# TwoMegCoCo_MMU_v1_1.net
KiCad netlist of a schematic drawn in EAGLE
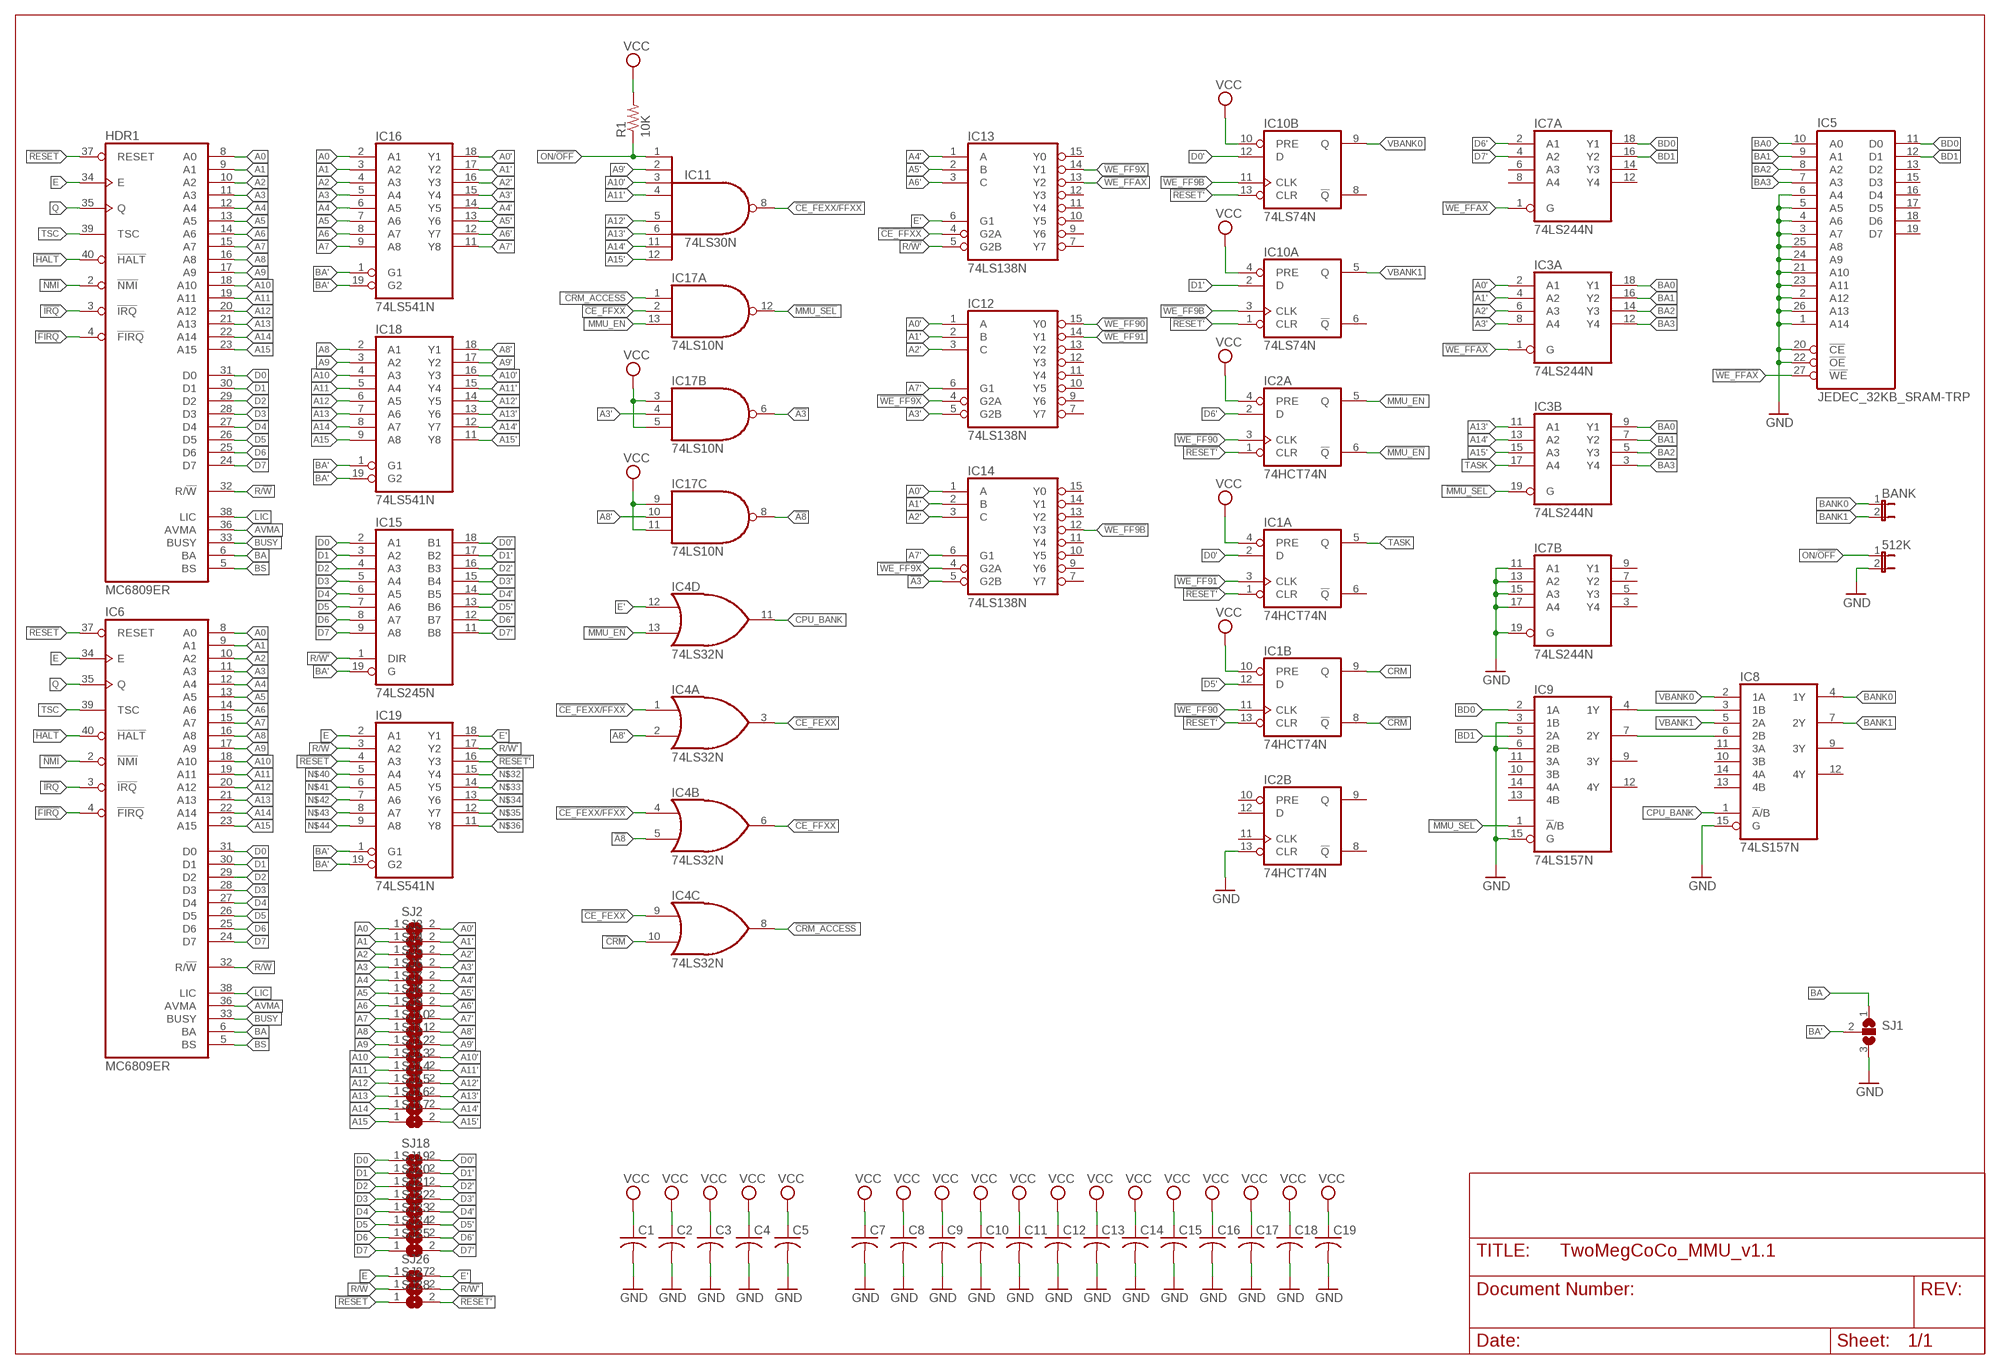
[diagram p0: schematic, sheet 1]

(export (version "E")
  (design (tool "Eeschema 10.0.6"))
  (components
    (comp (ref "512K")
      (value "JP1E")
      (footprint "eagle-import:JP1")
      (libsource (lib "eagle-import") (part "JP1E"))
    )
    (comp (ref "BANK")
      (value "JP1E")
      (footprint "eagle-import:JP1")
      (libsource (lib "eagle-import") (part "JP1E"))
    )
    (comp (ref "C1")
      (value "C-US025-025X050")
      (footprint "eagle-import:C025-025X050")
      (libsource (lib "eagle-import") (part "C-US025-025X050"))
    )
    (comp (ref "C2")
      (value "C-US025-025X050")
      (footprint "eagle-import:C025-025X050")
      (libsource (lib "eagle-import") (part "C-US025-025X050"))
    )
    (comp (ref "C3")
      (value "C-US025-025X050")
      (footprint "eagle-import:C025-025X050")
      (libsource (lib "eagle-import") (part "C-US025-025X050"))
    )
    (comp (ref "C4")
      (value "C-US025-025X050")
      (footprint "eagle-import:C025-025X050")
      (libsource (lib "eagle-import") (part "C-US025-025X050"))
    )
    (comp (ref "C5")
      (value "C-US025-025X050")
      (footprint "eagle-import:C025-025X050")
      (libsource (lib "eagle-import") (part "C-US025-025X050"))
    )
    (comp (ref "C7")
      (value "C-US025-025X050")
      (footprint "eagle-import:C025-025X050")
      (libsource (lib "eagle-import") (part "C-US025-025X050"))
    )
    (comp (ref "C8")
      (value "C-US025-025X050")
      (footprint "eagle-import:C025-025X050")
      (libsource (lib "eagle-import") (part "C-US025-025X050"))
    )
    (comp (ref "C9")
      (value "C-US025-025X050")
      (footprint "eagle-import:C025-025X050")
      (libsource (lib "eagle-import") (part "C-US025-025X050"))
    )
    (comp (ref "C10")
      (value "C-US025-025X050")
      (footprint "eagle-import:C025-025X050")
      (libsource (lib "eagle-import") (part "C-US025-025X050"))
    )
    (comp (ref "C11")
      (value "C-US025-025X050")
      (footprint "eagle-import:C025-025X050")
      (libsource (lib "eagle-import") (part "C-US025-025X050"))
    )
    (comp (ref "C12")
      (value "C-US025-025X050")
      (footprint "eagle-import:C025-025X050")
      (libsource (lib "eagle-import") (part "C-US025-025X050"))
    )
    (comp (ref "C13")
      (value "C-US025-025X050")
      (footprint "eagle-import:C025-025X050")
      (libsource (lib "eagle-import") (part "C-US025-025X050"))
    )
    (comp (ref "C14")
      (value "C-US025-025X050")
      (footprint "eagle-import:C025-025X050")
      (libsource (lib "eagle-import") (part "C-US025-025X050"))
    )
    (comp (ref "C15")
      (value "C-US025-025X050")
      (footprint "eagle-import:C025-025X050")
      (libsource (lib "eagle-import") (part "C-US025-025X050"))
    )
    (comp (ref "C16")
      (value "C-US025-025X050")
      (footprint "eagle-import:C025-025X050")
      (libsource (lib "eagle-import") (part "C-US025-025X050"))
    )
    (comp (ref "C17")
      (value "C-US025-025X050")
      (footprint "eagle-import:C025-025X050")
      (libsource (lib "eagle-import") (part "C-US025-025X050"))
    )
    (comp (ref "C18")
      (value "C-US025-025X050")
      (footprint "eagle-import:C025-025X050")
      (libsource (lib "eagle-import") (part "C-US025-025X050"))
    )
    (comp (ref "C19")
      (value "C-US025-025X050")
      (footprint "eagle-import:C025-025X050")
      (libsource (lib "eagle-import") (part "C-US025-025X050"))
    )
    (comp (ref "HDR1")
      (value "MC6809ER")
      (footprint "eagle-import:DIL40-ROUNDPAD")
      (libsource (lib "eagle-import") (part "MC6809ER"))
    )
    (comp (ref "IC1")
      (value "74HCT74N")
      (footprint "eagle-import:DIL14-RP")
      (libsource (lib "eagle-import") (part "7474NHCT"))
    )
    (comp (ref "IC2")
      (value "74HCT74N")
      (footprint "eagle-import:DIL14-RP")
      (libsource (lib "eagle-import") (part "7474NHCT"))
    )
    (comp (ref "IC3")
      (value "74LS244N")
      (footprint "eagle-import:DIL20-RP")
      (libsource (lib "eagle-import") (part "74244NLS"))
    )
    (comp (ref "IC4")
      (value "74LS32N")
      (footprint "eagle-import:DIL14-RP")
      (libsource (lib "eagle-import") (part "7432NLS"))
    )
    (comp (ref "IC5")
      (value "JEDEC_32KB_SRAM-TRP")
      (footprint "eagle-import:DIL28-3-RP")
      (libsource (lib "eagle-import") (part "JEDEC_32KB_SRAM-TRP"))
    )
    (comp (ref "IC6")
      (value "MC6809ER")
      (footprint "eagle-import:DIL40-ROUNDPAD")
      (libsource (lib "eagle-import") (part "MC6809ER"))
    )
    (comp (ref "IC7")
      (value "74LS244N")
      (footprint "eagle-import:DIL20-RP")
      (libsource (lib "eagle-import") (part "74244NLS"))
    )
    (comp (ref "IC8")
      (value "74LS157N")
      (footprint "eagle-import:DIL16-RP")
      (libsource (lib "eagle-import") (part "74157NLS"))
    )
    (comp (ref "IC9")
      (value "74LS157N")
      (footprint "eagle-import:DIL16-RP")
      (libsource (lib "eagle-import") (part "74157NLS"))
    )
    (comp (ref "IC10")
      (value "74LS74N")
      (footprint "eagle-import:DIL14-RP")
      (libsource (lib "eagle-import") (part "7474NLS"))
    )
    (comp (ref "IC11")
      (value "74LS30N")
      (footprint "eagle-import:DIL14-RP")
      (libsource (lib "eagle-import") (part "7430NLS"))
    )
    (comp (ref "IC12")
      (value "74LS138N")
      (footprint "eagle-import:DIL16-RP")
      (libsource (lib "eagle-import") (part "74138NLS"))
    )
    (comp (ref "IC13")
      (value "74LS138N")
      (footprint "eagle-import:DIL16-RP")
      (libsource (lib "eagle-import") (part "74138NLS"))
    )
    (comp (ref "IC14")
      (value "74LS138N")
      (footprint "eagle-import:DIL16-RP")
      (libsource (lib "eagle-import") (part "74138NLS"))
    )
    (comp (ref "IC15")
      (value "74LS245N")
      (footprint "eagle-import:DIL20-RP")
      (libsource (lib "eagle-import") (part "74245NLS"))
    )
    (comp (ref "IC16")
      (value "74LS541N")
      (footprint "eagle-import:DIL20-RP")
      (libsource (lib "eagle-import") (part "74541NLS"))
    )
    (comp (ref "IC17")
      (value "74LS10N")
      (footprint "eagle-import:DIL14-RP")
      (libsource (lib "eagle-import") (part "7410NLS"))
    )
    (comp (ref "IC18")
      (value "74LS541N")
      (footprint "eagle-import:DIL20-RP")
      (libsource (lib "eagle-import") (part "74541NLS"))
    )
    (comp (ref "IC19")
      (value "74LS541N")
      (footprint "eagle-import:DIL20-RP")
      (libsource (lib "eagle-import") (part "74541NLS"))
    )
    (comp (ref "R1")
      (value "10K")
      (footprint "eagle-import:0204_7")
      (libsource (lib "eagle-import") (part "R-US_0204/7"))
    )
    (comp (ref "SJ1")
      (value "SJ2W")
      (footprint "eagle-import:SJ_2")
      (libsource (lib "eagle-import") (part "SJ2W"))
    )
    (comp (ref "SJ2") (value "SJ") (footprint "eagle-import:SJ") (libsource (lib "eagle-import") (part "SJ")))
    (comp (ref "SJ3") (value "SJ") (footprint "eagle-import:SJ") (libsource (lib "eagle-import") (part "SJ")))
    (comp (ref "SJ4") (value "SJ") (footprint "eagle-import:SJ") (libsource (lib "eagle-import") (part "SJ")))
    (comp (ref "SJ5") (value "SJ") (footprint "eagle-import:SJ") (libsource (lib "eagle-import") (part "SJ")))
    (comp (ref "SJ6") (value "SJ") (footprint "eagle-import:SJ") (libsource (lib "eagle-import") (part "SJ")))
    (comp (ref "SJ7") (value "SJ") (footprint "eagle-import:SJ") (libsource (lib "eagle-import") (part "SJ")))
    (comp (ref "SJ8") (value "SJ") (footprint "eagle-import:SJ") (libsource (lib "eagle-import") (part "SJ")))
    (comp (ref "SJ9") (value "SJ") (footprint "eagle-import:SJ") (libsource (lib "eagle-import") (part "SJ")))
    (comp (ref "SJ10")
      (value "SJ")
      (footprint "eagle-import:SJ")
      (libsource (lib "eagle-import") (part "SJ"))
    )
    (comp (ref "SJ11")
      (value "SJ")
      (footprint "eagle-import:SJ")
      (libsource (lib "eagle-import") (part "SJ"))
    )
    (comp (ref "SJ12")
      (value "SJ")
      (footprint "eagle-import:SJ")
      (libsource (lib "eagle-import") (part "SJ"))
    )
    (comp (ref "SJ13")
      (value "SJ")
      (footprint "eagle-import:SJ")
      (libsource (lib "eagle-import") (part "SJ"))
    )
    (comp (ref "SJ14")
      (value "SJ")
      (footprint "eagle-import:SJ")
      (libsource (lib "eagle-import") (part "SJ"))
    )
    (comp (ref "SJ15")
      (value "SJ")
      (footprint "eagle-import:SJ")
      (libsource (lib "eagle-import") (part "SJ"))
    )
    (comp (ref "SJ16")
      (value "SJ")
      (footprint "eagle-import:SJ")
      (libsource (lib "eagle-import") (part "SJ"))
    )
    (comp (ref "SJ17")
      (value "SJ")
      (footprint "eagle-import:SJ")
      (libsource (lib "eagle-import") (part "SJ"))
    )
    (comp (ref "SJ18")
      (value "SJ")
      (footprint "eagle-import:SJ")
      (libsource (lib "eagle-import") (part "SJ"))
    )
    (comp (ref "SJ19")
      (value "SJ")
      (footprint "eagle-import:SJ")
      (libsource (lib "eagle-import") (part "SJ"))
    )
    (comp (ref "SJ20")
      (value "SJ")
      (footprint "eagle-import:SJ")
      (libsource (lib "eagle-import") (part "SJ"))
    )
    (comp (ref "SJ21")
      (value "SJ")
      (footprint "eagle-import:SJ")
      (libsource (lib "eagle-import") (part "SJ"))
    )
    (comp (ref "SJ22")
      (value "SJ")
      (footprint "eagle-import:SJ")
      (libsource (lib "eagle-import") (part "SJ"))
    )
    (comp (ref "SJ23")
      (value "SJ")
      (footprint "eagle-import:SJ")
      (libsource (lib "eagle-import") (part "SJ"))
    )
    (comp (ref "SJ24")
      (value "SJ")
      (footprint "eagle-import:SJ")
      (libsource (lib "eagle-import") (part "SJ"))
    )
    (comp (ref "SJ25")
      (value "SJ")
      (footprint "eagle-import:SJ")
      (libsource (lib "eagle-import") (part "SJ"))
    )
    (comp (ref "SJ26")
      (value "SJ")
      (footprint "eagle-import:SJ")
      (libsource (lib "eagle-import") (part "SJ"))
    )
    (comp (ref "SJ27")
      (value "SJ")
      (footprint "eagle-import:SJ")
      (libsource (lib "eagle-import") (part "SJ"))
    )
    (comp (ref "SJ28")
      (value "SJ")
      (footprint "eagle-import:SJ")
      (libsource (lib "eagle-import") (part "SJ"))
    )
  )
  (nets
    (net (code "1") (name "/ON{slash}~{OFF}") (class "Default")
      (node (ref "512K") (pin "1") (pinfunction "1_1") (pintype "passive"))
      (node (ref "IC11") (pin "1") (pinfunction "I0_1") (pintype "input"))
      (node (ref "R1") (pin "1") (pinfunction "1_1") (pintype "passive"))
    )
    (net (code "2") (name "/R{slash}~{W'}") (class "Default")
      (node (ref "IC13") (pin "5") (pinfunction "G2B_5") (pintype "input"))
      (node (ref "IC15") (pin "1") (pinfunction "DIR_1") (pintype "input"))
      (node (ref "IC19") (pin "17") (pinfunction "Y2_17") (pintype "tri_state"))
      (node (ref "SJ27") (pin "2") (pinfunction "2_2") (pintype "passive"))
    )
    (net (code "3") (name "/R{slash}~{W}") (class "Default")
      (node (ref "HDR1") (pin "32") (pinfunction "R/~{W}_32") (pintype "output"))
      (node (ref "IC19") (pin "3") (pinfunction "A2_3") (pintype "input"))
      (node (ref "IC6") (pin "32") (pinfunction "R/~{W}_32") (pintype "output"))
      (node (ref "SJ27") (pin "1") (pinfunction "1_1") (pintype "passive"))
    )
    (net (code "4") (name "/~{A3}") (class "Default")
      (node (ref "IC14") (pin "5") (pinfunction "G2B_5") (pintype "input"))
      (node (ref "IC17") (pin "6") (pinfunction "O_6") (pintype "output"))
    )
    (net (code "5") (name "/~{A8}") (class "Default")
      (node (ref "IC17") (pin "8") (pinfunction "O_8") (pintype "output"))
      (node (ref "IC4") (pin "5") (pinfunction "I1_5") (pintype "input"))
    )
    (net (code "6") (name "/~{CE_FEXX{slash}FFXX}") (class "Default")
      (node (ref "IC11") (pin "8") (pinfunction "O_8") (pintype "output"))
      (node (ref "IC4") (pin "1") (pinfunction "I0_1") (pintype "input"))
      (node (ref "IC4") (pin "4") (pinfunction "I0_4") (pintype "input"))
    )
    (net (code "7") (name "/~{CE_FEXX}") (class "Default")
      (node (ref "IC4") (pin "3") (pinfunction "O_3") (pintype "output"))
      (node (ref "IC4") (pin "9") (pinfunction "I0_9") (pintype "input"))
    )
    (net (code "8") (name "/~{CE_FFXX}") (class "Default")
      (node (ref "IC13") (pin "4") (pinfunction "G2A_4") (pintype "input"))
      (node (ref "IC17") (pin "2") (pinfunction "I1_2") (pintype "input"))
      (node (ref "IC4") (pin "6") (pinfunction "O_6") (pintype "output"))
    )
    (net (code "9") (name "/~{CRM_ACCESS}") (class "Default")
      (node (ref "IC17") (pin "1") (pinfunction "I0_1") (pintype "input"))
      (node (ref "IC4") (pin "8") (pinfunction "O_8") (pintype "output"))
    )
    (net (code "10") (name "/~{CRM}") (class "Default")
      (node (ref "IC1") (pin "8") (pinfunction "~{Q}_8") (pintype "output"))
      (node (ref "IC4") (pin "10") (pinfunction "I1_10") (pintype "input"))
    )
    (net (code "11") (name "/~{FIRQ}") (class "Default")
      (node (ref "HDR1") (pin "4") (pinfunction "~{FIRQ}_4") (pintype "open_collector"))
      (node (ref "IC6") (pin "4") (pinfunction "~{FIRQ}_4") (pintype "open_collector"))
    )
    (net (code "12") (name "/~{HALT}") (class "Default")
      (node (ref "HDR1") (pin "40") (pinfunction "~{HALT}_40") (pintype "open_collector"))
      (node (ref "IC6") (pin "40") (pinfunction "~{HALT}_40") (pintype "open_collector"))
    )
    (net (code "13") (name "/~{IRQ}") (class "Default")
      (node (ref "HDR1") (pin "3") (pinfunction "~{IRQ}_3") (pintype "open_collector"))
      (node (ref "IC6") (pin "3") (pinfunction "~{IRQ}_3") (pintype "open_collector"))
    )
    (net (code "14") (name "/~{MMU_EN}") (class "Default")
      (node (ref "IC2") (pin "6") (pinfunction "~{Q}_6") (pintype "output"))
      (node (ref "IC4") (pin "13") (pinfunction "I1_13") (pintype "input"))
    )
    (net (code "15") (name "/~{MMU_SEL}") (class "Default")
      (node (ref "IC17") (pin "12") (pinfunction "O_12") (pintype "output"))
      (node (ref "IC3") (pin "19") (pinfunction "G_19") (pintype "input"))
      (node (ref "IC9") (pin "1") (pinfunction "~{A}/B_1") (pintype "input"))
    )
    (net (code "16") (name "/~{NMI}") (class "Default")
      (node (ref "HDR1") (pin "2") (pinfunction "~{NMI}_2") (pintype "open_collector"))
      (node (ref "IC6") (pin "2") (pinfunction "~{NMI}_2") (pintype "open_collector"))
    )
    (net (code "17") (name "/~{RESET'}") (class "Default")
      (node (ref "IC1") (pin "1") (pinfunction "CLR_1") (pintype "input"))
      (node (ref "IC1") (pin "13") (pinfunction "CLR_13") (pintype "input"))
      (node (ref "IC10") (pin "1") (pinfunction "CLR_1") (pintype "input"))
      (node (ref "IC10") (pin "13") (pinfunction "CLR_13") (pintype "input"))
      (node (ref "IC19") (pin "16") (pinfunction "Y3_16") (pintype "tri_state"))
      (node (ref "IC2") (pin "1") (pinfunction "CLR_1") (pintype "input"))
      (node (ref "SJ28") (pin "2") (pinfunction "2_2") (pintype "passive"))
    )
    (net (code "18") (name "/~{RESET}") (class "Default")
      (node (ref "HDR1") (pin "37") (pinfunction "RESET_37") (pintype "input"))
      (node (ref "IC19") (pin "4") (pinfunction "A3_4") (pintype "input"))
      (node (ref "IC6") (pin "37") (pinfunction "RESET_37") (pintype "input"))
      (node (ref "SJ28") (pin "1") (pinfunction "1_1") (pintype "passive"))
    )
    (net (code "19") (name "/~{WE_FF9B}") (class "Default")
      (node (ref "IC10") (pin "11") (pinfunction "CLK_11") (pintype "input"))
      (node (ref "IC10") (pin "3") (pinfunction "CLK_3") (pintype "input"))
      (node (ref "IC14") (pin "12") (pinfunction "Y3_12") (pintype "output"))
    )
    (net (code "20") (name "/~{WE_FF9X}") (class "Default")
      (node (ref "IC12") (pin "4") (pinfunction "G2A_4") (pintype "input"))
      (node (ref "IC13") (pin "14") (pinfunction "Y1_14") (pintype "output"))
      (node (ref "IC14") (pin "4") (pinfunction "G2A_4") (pintype "input"))
    )
    (net (code "21") (name "/~{WE_FF90}") (class "Default")
      (node (ref "IC1") (pin "11") (pinfunction "CLK_11") (pintype "input"))
      (node (ref "IC12") (pin "15") (pinfunction "Y0_15") (pintype "output"))
      (node (ref "IC2") (pin "3") (pinfunction "CLK_3") (pintype "input"))
    )
    (net (code "22") (name "/~{WE_FF91}") (class "Default")
      (node (ref "IC1") (pin "3") (pinfunction "CLK_3") (pintype "input"))
      (node (ref "IC12") (pin "14") (pinfunction "Y1_14") (pintype "output"))
    )
    (net (code "23") (name "/~{WE_FFAX}") (class "Default")
      (node (ref "IC13") (pin "13") (pinfunction "Y2_13") (pintype "output"))
      (node (ref "IC3") (pin "1") (pinfunction "G_1") (pintype "input"))
      (node (ref "IC5") (pin "27") (pinfunction "~{WE}_27") (pintype "input"))
      (node (ref "IC7") (pin "1") (pinfunction "G_1") (pintype "input"))
    )
    (net (code "24") (name "A0") (class "Default")
      (node (ref "HDR1") (pin "8") (pinfunction "A0_8") (pintype "tri_state"))
      (node (ref "IC16") (pin "2") (pinfunction "A1_2") (pintype "input"))
      (node (ref "IC6") (pin "8") (pinfunction "A0_8") (pintype "tri_state"))
      (node (ref "SJ2") (pin "1") (pinfunction "1_1") (pintype "passive"))
    )
    (net (code "25") (name "A0'") (class "Default")
      (node (ref "IC12") (pin "1") (pinfunction "A_1") (pintype "input"))
      (node (ref "IC14") (pin "1") (pinfunction "A_1") (pintype "input"))
      (node (ref "IC16") (pin "18") (pinfunction "Y1_18") (pintype "tri_state"))
      (node (ref "IC3") (pin "2") (pinfunction "A1_2") (pintype "input"))
      (node (ref "SJ2") (pin "2") (pinfunction "2_2") (pintype "passive"))
    )
    (net (code "26") (name "A1") (class "Default")
      (node (ref "HDR1") (pin "9") (pinfunction "A1_9") (pintype "tri_state"))
      (node (ref "IC16") (pin "3") (pinfunction "A2_3") (pintype "input"))
      (node (ref "IC6") (pin "9") (pinfunction "A1_9") (pintype "tri_state"))
      (node (ref "SJ3") (pin "1") (pinfunction "1_1") (pintype "passive"))
    )
    (net (code "27") (name "A1'") (class "Default")
      (node (ref "IC12") (pin "2") (pinfunction "B_2") (pintype "input"))
      (node (ref "IC14") (pin "2") (pinfunction "B_2") (pintype "input"))
      (node (ref "IC16") (pin "17") (pinfunction "Y2_17") (pintype "tri_state"))
      (node (ref "IC3") (pin "4") (pinfunction "A2_4") (pintype "input"))
      (node (ref "SJ3") (pin "2") (pinfunction "2_2") (pintype "passive"))
    )
    (net (code "28") (name "A2") (class "Default")
      (node (ref "HDR1") (pin "10") (pinfunction "A2_10") (pintype "tri_state"))
      (node (ref "IC16") (pin "4") (pinfunction "A3_4") (pintype "input"))
      (node (ref "IC6") (pin "10") (pinfunction "A2_10") (pintype "tri_state"))
      (node (ref "SJ4") (pin "1") (pinfunction "1_1") (pintype "passive"))
    )
    (net (code "29") (name "A2'") (class "Default")
      (node (ref "IC12") (pin "3") (pinfunction "C_3") (pintype "input"))
      (node (ref "IC14") (pin "3") (pinfunction "C_3") (pintype "input"))
      (node (ref "IC16") (pin "16") (pinfunction "Y3_16") (pintype "tri_state"))
      (node (ref "IC3") (pin "6") (pinfunction "A3_6") (pintype "input"))
      (node (ref "SJ4") (pin "2") (pinfunction "2_2") (pintype "passive"))
    )
    (net (code "30") (name "A3") (class "Default")
      (node (ref "HDR1") (pin "11") (pinfunction "A3_11") (pintype "tri_state"))
      (node (ref "IC16") (pin "5") (pinfunction "A4_5") (pintype "input"))
      (node (ref "IC6") (pin "11") (pinfunction "A3_11") (pintype "tri_state"))
      (node (ref "SJ5") (pin "1") (pinfunction "1_1") (pintype "passive"))
    )
    (net (code "31") (name "A3'") (class "Default")
      (node (ref "IC12") (pin "5") (pinfunction "G2B_5") (pintype "input"))
      (node (ref "IC16") (pin "15") (pinfunction "Y4_15") (pintype "tri_state"))
      (node (ref "IC17") (pin "4") (pinfunction "I1_4") (pintype "input"))
      (node (ref "IC3") (pin "8") (pinfunction "A4_8") (pintype "input"))
      (node (ref "SJ5") (pin "2") (pinfunction "2_2") (pintype "passive"))
    )
    (net (code "32") (name "A4") (class "Default")
      (node (ref "HDR1") (pin "12") (pinfunction "A4_12") (pintype "tri_state"))
      (node (ref "IC16") (pin "6") (pinfunction "A5_6") (pintype "input"))
      (node (ref "IC6") (pin "12") (pinfunction "A4_12") (pintype "tri_state"))
      (node (ref "SJ6") (pin "1") (pinfunction "1_1") (pintype "passive"))
    )
    (net (code "33") (name "A4'") (class "Default")
      (node (ref "IC13") (pin "1") (pinfunction "A_1") (pintype "input"))
      (node (ref "IC16") (pin "14") (pinfunction "Y5_14") (pintype "tri_state"))
      (node (ref "SJ6") (pin "2") (pinfunction "2_2") (pintype "passive"))
    )
    (net (code "34") (name "A5") (class "Default")
      (node (ref "HDR1") (pin "13") (pinfunction "A5_13") (pintype "tri_state"))
      (node (ref "IC16") (pin "7") (pinfunction "A6_7") (pintype "input"))
      (node (ref "IC6") (pin "13") (pinfunction "A5_13") (pintype "tri_state"))
      (node (ref "SJ7") (pin "1") (pinfunction "1_1") (pintype "passive"))
    )
    (net (code "35") (name "A5'") (class "Default")
      (node (ref "IC13") (pin "2") (pinfunction "B_2") (pintype "input"))
      (node (ref "IC16") (pin "13") (pinfunction "Y6_13") (pintype "tri_state"))
      (node (ref "SJ7") (pin "2") (pinfunction "2_2") (pintype "passive"))
    )
    (net (code "36") (name "A6") (class "Default")
      (node (ref "HDR1") (pin "14") (pinfunction "A6_14") (pintype "tri_state"))
      (node (ref "IC16") (pin "8") (pinfunction "A7_8") (pintype "input"))
      (node (ref "IC6") (pin "14") (pinfunction "A6_14") (pintype "tri_state"))
      (node (ref "SJ8") (pin "1") (pinfunction "1_1") (pintype "passive"))
    )
    (net (code "37") (name "A6'") (class "Default")
      (node (ref "IC13") (pin "3") (pinfunction "C_3") (pintype "input"))
      (node (ref "IC16") (pin "12") (pinfunction "Y7_12") (pintype "tri_state"))
      (node (ref "SJ8") (pin "2") (pinfunction "2_2") (pintype "passive"))
    )
    (net (code "38") (name "A7") (class "Default")
      (node (ref "HDR1") (pin "15") (pinfunction "A7_15") (pintype "tri_state"))
      (node (ref "IC16") (pin "9") (pinfunction "A8_9") (pintype "input"))
      (node (ref "IC6") (pin "15") (pinfunction "A7_15") (pintype "tri_state"))
      (node (ref "SJ9") (pin "1") (pinfunction "1_1") (pintype "passive"))
    )
    (net (code "39") (name "A7'") (class "Default")
      (node (ref "IC12") (pin "6") (pinfunction "G1_6") (pintype "input"))
      (node (ref "IC14") (pin "6") (pinfunction "G1_6") (pintype "input"))
      (node (ref "IC16") (pin "11") (pinfunction "Y8_11") (pintype "tri_state"))
      (node (ref "SJ9") (pin "2") (pinfunction "2_2") (pintype "passive"))
    )
    (net (code "40") (name "A8") (class "Default")
      (node (ref "HDR1") (pin "16") (pinfunction "A8_16") (pintype "tri_state"))
      (node (ref "IC18") (pin "2") (pinfunction "A1_2") (pintype "input"))
      (node (ref "IC6") (pin "16") (pinfunction "A8_16") (pintype "tri_state"))
      (node (ref "SJ10") (pin "1") (pinfunction "1_1") (pintype "passive"))
    )
    (net (code "41") (name "A8'") (class "Default")
      (node (ref "IC17") (pin "10") (pinfunction "I1_10") (pintype "input"))
      (node (ref "IC18") (pin "18") (pinfunction "Y1_18") (pintype "tri_state"))
      (node (ref "IC4") (pin "2") (pinfunction "I1_2") (pintype "input"))
      (node (ref "SJ10") (pin "2") (pinfunction "2_2") (pintype "passive"))
    )
    (net (code "42") (name "A9") (class "Default")
      (node (ref "HDR1") (pin "17") (pinfunction "A9_17") (pintype "tri_state"))
      (node (ref "IC18") (pin "3") (pinfunction "A2_3") (pintype "input"))
      (node (ref "IC6") (pin "17") (pinfunction "A9_17") (pintype "tri_state"))
      (node (ref "SJ11") (pin "1") (pinfunction "1_1") (pintype "passive"))
    )
    (net (code "43") (name "A9'") (class "Default")
      (node (ref "IC11") (pin "2") (pinfunction "I1_2") (pintype "input"))
      (node (ref "IC18") (pin "17") (pinfunction "Y2_17") (pintype "tri_state"))
      (node (ref "SJ11") (pin "2") (pinfunction "2_2") (pintype "passive"))
    )
    (net (code "44") (name "A10") (class "Default")
      (node (ref "HDR1") (pin "18") (pinfunction "A10_18") (pintype "tri_state"))
      (node (ref "IC18") (pin "4") (pinfunction "A3_4") (pintype "input"))
      (node (ref "IC6") (pin "18") (pinfunction "A10_18") (pintype "tri_state"))
      (node (ref "SJ12") (pin "1") (pinfunction "1_1") (pintype "passive"))
    )
    (net (code "45") (name "A10'") (class "Default")
      (node (ref "IC11") (pin "3") (pinfunction "I2_3") (pintype "input"))
      (node (ref "IC18") (pin "16") (pinfunction "Y3_16") (pintype "tri_state"))
      (node (ref "SJ12") (pin "2") (pinfunction "2_2") (pintype "passive"))
    )
    (net (code "46") (name "A11") (class "Default")
      (node (ref "HDR1") (pin "19") (pinfunction "A11_19") (pintype "tri_state"))
      (node (ref "IC18") (pin "5") (pinfunction "A4_5") (pintype "input"))
      (node (ref "IC6") (pin "19") (pinfunction "A11_19") (pintype "tri_state"))
      (node (ref "SJ13") (pin "1") (pinfunction "1_1") (pintype "passive"))
    )
    (net (code "47") (name "A11'") (class "Default")
      (node (ref "IC11") (pin "4") (pinfunction "I3_4") (pintype "input"))
      (node (ref "IC18") (pin "15") (pinfunction "Y4_15") (pintype "tri_state"))
      (node (ref "SJ13") (pin "2") (pinfunction "2_2") (pintype "passive"))
    )
    (net (code "48") (name "A12") (class "Default")
      (node (ref "HDR1") (pin "20") (pinfunction "A12_20") (pintype "tri_state"))
      (node (ref "IC18") (pin "6") (pinfunction "A5_6") (pintype "input"))
      (node (ref "IC6") (pin "20") (pinfunction "A12_20") (pintype "tri_state"))
      (node (ref "SJ14") (pin "1") (pinfunction "1_1") (pintype "passive"))
    )
    (net (code "49") (name "A12'") (class "Default")
      (node (ref "IC11") (pin "5") (pinfunction "I4_5") (pintype "input"))
      (node (ref "IC18") (pin "14") (pinfunction "Y5_14") (pintype "tri_state"))
      (node (ref "SJ14") (pin "2") (pinfunction "2_2") (pintype "passive"))
    )
    (net (code "50") (name "A13") (class "Default")
      (node (ref "HDR1") (pin "21") (pinfunction "A13_21") (pintype "tri_state"))
      (node (ref "IC18") (pin "7") (pinfunction "A6_7") (pintype "input"))
      (node (ref "IC6") (pin "21") (pinfunction "A13_21") (pintype "tri_state"))
      (node (ref "SJ15") (pin "1") (pinfunction "1_1") (pintype "passive"))
    )
    (net (code "51") (name "A13'") (class "Default")
      (node (ref "IC11") (pin "6") (pinfunction "I5_6") (pintype "input"))
      (node (ref "IC18") (pin "13") (pinfunction "Y6_13") (pintype "tri_state"))
      (node (ref "IC3") (pin "11") (pinfunction "A1_11") (pintype "input"))
      (node (ref "SJ15") (pin "2") (pinfunction "2_2") (pintype "passive"))
    )
    (net (code "52") (name "A14") (class "Default")
      (node (ref "HDR1") (pin "22") (pinfunction "A14_22") (pintype "tri_state"))
      (node (ref "IC18") (pin "8") (pinfunction "A7_8") (pintype "input"))
      (node (ref "IC6") (pin "22") (pinfunction "A14_22") (pintype "tri_state"))
      (node (ref "SJ16") (pin "1") (pinfunction "1_1") (pintype "passive"))
    )
    (net (code "53") (name "A14'") (class "Default")
      (node (ref "IC11") (pin "11") (pinfunction "I6_11") (pintype "input"))
      (node (ref "IC18") (pin "12") (pinfunction "Y7_12") (pintype "tri_state"))
      (node (ref "IC3") (pin "13") (pinfunction "A2_13") (pintype "input"))
      (node (ref "SJ16") (pin "2") (pinfunction "2_2") (pintype "passive"))
    )
    (net (code "54") (name "A15") (class "Default")
      (node (ref "HDR1") (pin "23") (pinfunction "A15_23") (pintype "tri_state"))
      (node (ref "IC18") (pin "9") (pinfunction "A8_9") (pintype "input"))
      (node (ref "IC6") (pin "23") (pinfunction "A15_23") (pintype "tri_state"))
      (node (ref "SJ17") (pin "1") (pinfunction "1_1") (pintype "passive"))
    )
    (net (code "55") (name "A15'") (class "Default")
      (node (ref "IC11") (pin "12") (pinfunction "I7_12") (pintype "input"))
      (node (ref "IC18") (pin "11") (pinfunction "Y8_11") (pintype "tri_state"))
      (node (ref "IC3") (pin "15") (pinfunction "A3_15") (pintype "input"))
      (node (ref "SJ17") (pin "2") (pinfunction "2_2") (pintype "passive"))
    )
    (net (code "56") (name "AVMA") (class "Default")
      (node (ref "HDR1") (pin "36") (pinfunction "AVMA_36") (pintype "output"))
      (node (ref "IC6") (pin "36") (pinfunction "AVMA_36") (pintype "output"))
    )
    (net (code "57") (name "BA") (class "Default")
      (node (ref "HDR1") (pin "6") (pinfunction "BA_6") (pintype "output"))
      (node (ref "IC6") (pin "6") (pinfunction "BA_6") (pintype "output"))
      (node (ref "SJ1") (pin "1") (pinfunction "1_1") (pintype "passive"))
    )
    (net (code "58") (name "BA'") (class "Default")
      (node (ref "IC15") (pin "19") (pinfunction "G_19") (pintype "input"))
      (node (ref "IC16") (pin "1") (pinfunction "G1_1") (pintype "input"))
      (node (ref "IC16") (pin "19") (pinfunction "G2_19") (pintype "input"))
      (node (ref "IC18") (pin "1") (pinfunction "G1_1") (pintype "input"))
      (node (ref "IC18") (pin "19") (pinfunction "G2_19") (pintype "input"))
      (node (ref "IC19") (pin "1") (pinfunction "G1_1") (pintype "input"))
      (node (ref "IC19") (pin "19") (pinfunction "G2_19") (pintype "input"))
      (node (ref "SJ1") (pin "2") (pinfunction "2_2") (pintype "passive"))
    )
    (net (code "59") (name "BA0") (class "Default")
      (node (ref "IC3") (pin "18") (pinfunction "Y1_18") (pintype "tri_state"))
      (node (ref "IC3") (pin "9") (pinfunction "Y1_9") (pintype "tri_state"))
      (node (ref "IC5") (pin "10") (pinfunction "A0_10") (pintype "input"))
    )
    (net (code "60") (name "BA1") (class "Default")
      (node (ref "IC3") (pin "16") (pinfunction "Y2_16") (pintype "tri_state"))
      (node (ref "IC3") (pin "7") (pinfunction "Y2_7") (pintype "tri_state"))
      (node (ref "IC5") (pin "9") (pinfunction "A1_9") (pintype "input"))
    )
    (net (code "61") (name "BA2") (class "Default")
      (node (ref "IC3") (pin "14") (pinfunction "Y3_14") (pintype "tri_state"))
      (node (ref "IC3") (pin "5") (pinfunction "Y3_5") (pintype "tri_state"))
      (node (ref "IC5") (pin "8") (pinfunction "A2_8") (pintype "input"))
    )
    (net (code "62") (name "BA3") (class "Default")
      (node (ref "IC3") (pin "12") (pinfunction "Y4_12") (pintype "tri_state"))
      (node (ref "IC3") (pin "3") (pinfunction "Y4_3") (pintype "tri_state"))
      (node (ref "IC5") (pin "7") (pinfunction "A3_7") (pintype "input"))
    )
    (net (code "63") (name "BANK0") (class "Default")
      (node (ref "BANK") (pin "1") (pinfunction "1_1") (pintype "passive"))
      (node (ref "IC8") (pin "4") (pinfunction "1Y_4") (pintype "output"))
    )
    (net (code "64") (name "BANK1") (class "Default")
      (node (ref "BANK") (pin "2") (pinfunction "2_2") (pintype "passive"))
      (node (ref "IC8") (pin "7") (pinfunction "2Y_7") (pintype "output"))
    )
    (net (code "65") (name "BD0") (class "Default")
      (node (ref "IC5") (pin "11") (pinfunction "D0_11") (pintype "bidirectional"))
      (node (ref "IC7") (pin "18") (pinfunction "Y1_18") (pintype "tri_state"))
      (node (ref "IC9") (pin "2") (pinfunction "1A_2") (pintype "input"))
    )
    (net (code "66") (name "BD1") (class "Default")
      (node (ref "IC5") (pin "12") (pinfunction "D1_12") (pintype "bidirectional"))
      (node (ref "IC7") (pin "16") (pinfunction "Y2_16") (pintype "tri_state"))
      (node (ref "IC9") (pin "5") (pinfunction "2A_5") (pintype "input"))
    )
    (net (code "67") (name "BS") (class "Default")
      (node (ref "HDR1") (pin "5") (pinfunction "BS_5") (pintype "output"))
      (node (ref "IC6") (pin "5") (pinfunction "BS_5") (pintype "output"))
    )
    (net (code "68") (name "BUSY") (class "Default")
      (node (ref "HDR1") (pin "33") (pinfunction "BUSY_33") (pintype "output"))
      (node (ref "IC6") (pin "33") (pinfunction "BUSY_33") (pintype "output"))
    )
    (net (code "69") (name "CPU_BANK") (class "Default")
      (node (ref "IC4") (pin "11") (pinfunction "O_11") (pintype "output"))
      (node (ref "IC8") (pin "1") (pinfunction "~{A}/B_1") (pintype "input"))
    )
    (net (code "70") (name "CRM") (class "Default")
      (node (ref "IC1") (pin "9") (pinfunction "Q_9") (pintype "output"))
    )
    (net (code "71") (name "D0") (class "Default")
      (node (ref "HDR1") (pin "31") (pinfunction "D0_31") (pintype "bidirectional"))
      (node (ref "IC15") (pin "2") (pinfunction "A1_2") (pintype "bidirectional"))
      (node (ref "IC6") (pin "31") (pinfunction "D0_31") (pintype "bidirectional"))
      (node (ref "SJ18") (pin "1") (pinfunction "1_1") (pintype "passive"))
    )
    (net (code "72") (name "D0'") (class "Default")
      (node (ref "IC1") (pin "2") (pinfunction "D_2") (pintype "input"))
      (node (ref "IC10") (pin "12") (pinfunction "D_12") (pintype "input"))
      (node (ref "IC15") (pin "18") (pinfunction "B1_18") (pintype "bidirectional"))
      (node (ref "SJ18") (pin "2") (pinfunction "2_2") (pintype "passive"))
    )
    (net (code "73") (name "D1") (class "Default")
      (node (ref "HDR1") (pin "30") (pinfunction "D1_30") (pintype "bidirectional"))
      (node (ref "IC15") (pin "3") (pinfunction "A2_3") (pintype "bidirectional"))
      (node (ref "IC6") (pin "30") (pinfunction "D1_30") (pintype "bidirectional"))
      (node (ref "SJ19") (pin "1") (pinfunction "1_1") (pintype "passive"))
    )
    (net (code "74") (name "D1'") (class "Default")
      (node (ref "IC10") (pin "2") (pinfunction "D_2") (pintype "input"))
      (node (ref "IC15") (pin "17") (pinfunction "B2_17") (pintype "bidirectional"))
      (node (ref "SJ19") (pin "2") (pinfunction "2_2") (pintype "passive"))
    )
    (net (code "75") (name "D2") (class "Default")
      (node (ref "HDR1") (pin "29") (pinfunction "D2_29") (pintype "bidirectional"))
      (node (ref "IC15") (pin "4") (pinfunction "A3_4") (pintype "bidirectional"))
      (node (ref "IC6") (pin "29") (pinfunction "D2_29") (pintype "bidirectional"))
      (node (ref "SJ20") (pin "1") (pinfunction "1_1") (pintype "passive"))
    )
    (net (code "76") (name "D2'") (class "Default")
      (node (ref "IC15") (pin "16") (pinfunction "B3_16") (pintype "bidirectional"))
      (node (ref "SJ20") (pin "2") (pinfunction "2_2") (pintype "passive"))
    )
    (net (code "77") (name "D3") (class "Default")
      (node (ref "HDR1") (pin "28") (pinfunction "D3_28") (pintype "bidirectional"))
      (node (ref "IC15") (pin "5") (pinfunction "A4_5") (pintype "bidirectional"))
      (node (ref "IC6") (pin "28") (pinfunction "D3_28") (pintype "bidirectional"))
      (node (ref "SJ21") (pin "1") (pinfunction "1_1") (pintype "passive"))
    )
    (net (code "78") (name "D3'") (class "Default")
      (node (ref "IC15") (pin "15") (pinfunction "B4_15") (pintype "bidirectional"))
      (node (ref "SJ21") (pin "2") (pinfunction "2_2") (pintype "passive"))
    )
    (net (code "79") (name "D4") (class "Default")
      (node (ref "HDR1") (pin "27") (pinfunction "D4_27") (pintype "bidirectional"))
      (node (ref "IC15") (pin "6") (pinfunction "A5_6") (pintype "bidirectional"))
      (node (ref "IC6") (pin "27") (pinfunction "D4_27") (pintype "bidirectional"))
      (node (ref "SJ22") (pin "1") (pinfunction "1_1") (pintype "passive"))
    )
    (net (code "80") (name "D4'") (class "Default")
      (node (ref "IC15") (pin "14") (pinfunction "B5_14") (pintype "bidirectional"))
      (node (ref "SJ22") (pin "2") (pinfunction "2_2") (pintype "passive"))
    )
    (net (code "81") (name "D5") (class "Default")
      (node (ref "HDR1") (pin "26") (pinfunction "D5_26") (pintype "bidirectional"))
      (node (ref "IC15") (pin "7") (pinfunction "A6_7") (pintype "bidirectional"))
      (node (ref "IC6") (pin "26") (pinfunction "D5_26") (pintype "bidirectional"))
      (node (ref "SJ23") (pin "1") (pinfunction "1_1") (pintype "passive"))
    )
    (net (code "82") (name "D5'") (class "Default")
      (node (ref "IC1") (pin "12") (pinfunction "D_12") (pintype "input"))
      (node (ref "IC15") (pin "13") (pinfunction "B6_13") (pintype "bidirectional"))
      (node (ref "SJ23") (pin "2") (pinfunction "2_2") (pintype "passive"))
    )
    (net (code "83") (name "D6") (class "Default")
      (node (ref "HDR1") (pin "25") (pinfunction "D6_25") (pintype "bidirectional"))
      (node (ref "IC15") (pin "8") (pinfunction "A7_8") (pintype "bidirectional"))
      (node (ref "IC6") (pin "25") (pinfunction "D6_25") (pintype "bidirectional"))
      (node (ref "SJ24") (pin "1") (pinfunction "1_1") (pintype "passive"))
    )
    (net (code "84") (name "D6'") (class "Default")
      (node (ref "IC15") (pin "12") (pinfunction "B7_12") (pintype "bidirectional"))
      (node (ref "IC2") (pin "2") (pinfunction "D_2") (pintype "input"))
      (node (ref "IC7") (pin "2") (pinfunction "A1_2") (pintype "input"))
      (node (ref "SJ24") (pin "2") (pinfunction "2_2") (pintype "passive"))
    )
    (net (code "85") (name "D7") (class "Default")
      (node (ref "HDR1") (pin "24") (pinfunction "D7_24") (pintype "bidirectional"))
      (node (ref "IC15") (pin "9") (pinfunction "A8_9") (pintype "bidirectional"))
      (node (ref "IC6") (pin "24") (pinfunction "D7_24") (pintype "bidirectional"))
      (node (ref "SJ25") (pin "1") (pinfunction "1_1") (pintype "passive"))
    )
    (net (code "86") (name "D7'") (class "Default")
      (node (ref "IC15") (pin "11") (pinfunction "B8_11") (pintype "bidirectional"))
      (node (ref "IC7") (pin "4") (pinfunction "A2_4") (pintype "input"))
      (node (ref "SJ25") (pin "2") (pinfunction "2_2") (pintype "passive"))
    )
    (net (code "87") (name "E") (class "Default")
      (node (ref "HDR1") (pin "34") (pinfunction "E_34") (pintype "input"))
      (node (ref "IC19") (pin "2") (pinfunction "A1_2") (pintype "input"))
      (node (ref "IC6") (pin "34") (pinfunction "E_34") (pintype "input"))
      (node (ref "SJ26") (pin "1") (pinfunction "1_1") (pintype "passive"))
    )
    (net (code "88") (name "E'") (class "Default")
      (node (ref "IC13") (pin "6") (pinfunction "G1_6") (pintype "input"))
      (node (ref "IC19") (pin "18") (pinfunction "Y1_18") (pintype "tri_state"))
      (node (ref "IC4") (pin "12") (pinfunction "I0_12") (pintype "input"))
      (node (ref "SJ26") (pin "2") (pinfunction "2_2") (pintype "passive"))
    )
    (net (code "89") (name "GND") (class "Default")
      (node (ref "512K") (pin "2") (pinfunction "2_2") (pintype "passive"))
      (node (ref "C1") (pin "2") (pinfunction "2_2") (pintype "passive"))
      (node (ref "C10") (pin "2") (pinfunction "2_2") (pintype "passive"))
      (node (ref "C11") (pin "2") (pinfunction "2_2") (pintype "passive"))
      (node (ref "C12") (pin "2") (pinfunction "2_2") (pintype "passive"))
      (node (ref "C13") (pin "2") (pinfunction "2_2") (pintype "passive"))
      (node (ref "C14") (pin "2") (pinfunction "2_2") (pintype "passive"))
      (node (ref "C15") (pin "2") (pinfunction "2_2") (pintype "passive"))
      (node (ref "C16") (pin "2") (pinfunction "2_2") (pintype "passive"))
      (node (ref "C17") (pin "2") (pinfunction "2_2") (pintype "passive"))
      (node (ref "C18") (pin "2") (pinfunction "2_2") (pintype "passive"))
      (node (ref "C19") (pin "2") (pinfunction "2_2") (pintype "passive"))
      (node (ref "C2") (pin "2") (pinfunction "2_2") (pintype "passive"))
      (node (ref "C3") (pin "2") (pinfunction "2_2") (pintype "passive"))
      (node (ref "C4") (pin "2") (pinfunction "2_2") (pintype "passive"))
      (node (ref "C5") (pin "2") (pinfunction "2_2") (pintype "passive"))
      (node (ref "C7") (pin "2") (pinfunction "2_2") (pintype "passive"))
      (node (ref "C8") (pin "2") (pinfunction "2_2") (pintype "passive"))
      (node (ref "C9") (pin "2") (pinfunction "2_2") (pintype "passive"))
      (node (ref "IC2") (pin "13") (pinfunction "CLR_13") (pintype "input"))
      (node (ref "IC5") (pin "1") (pinfunction "A14_1") (pintype "input"))
      (node (ref "IC5") (pin "2") (pinfunction "A12_2") (pintype "input"))
      (node (ref "IC5") (pin "20") (pinfunction "~{CE}_20") (pintype "input"))
      (node (ref "IC5") (pin "21") (pinfunction "A10_21") (pintype "input"))
      (node (ref "IC5") (pin "22") (pinfunction "~{OE}_22") (pintype "input"))
      (node (ref "IC5") (pin "23") (pinfunction "A11_23") (pintype "input"))
      (node (ref "IC5") (pin "24") (pinfunction "A9_24") (pintype "input"))
      (node (ref "IC5") (pin "25") (pinfunction "A8_25") (pintype "input"))
      (node (ref "IC5") (pin "26") (pinfunction "A13_26") (pintype "input"))
      (node (ref "IC5") (pin "3") (pinfunction "A7_3") (pintype "input"))
      (node (ref "IC5") (pin "4") (pinfunction "A6_4") (pintype "input"))
      (node (ref "IC5") (pin "5") (pinfunction "A5_5") (pintype "input"))
      (node (ref "IC5") (pin "6") (pinfunction "A4_6") (pintype "input"))
      (node (ref "IC7") (pin "11") (pinfunction "A1_11") (pintype "input"))
      (node (ref "IC7") (pin "13") (pinfunction "A2_13") (pintype "input"))
      (node (ref "IC7") (pin "15") (pinfunction "A3_15") (pintype "input"))
      (node (ref "IC7") (pin "17") (pinfunction "A4_17") (pintype "input"))
      (node (ref "IC7") (pin "19") (pinfunction "G_19") (pintype "input"))
      (node (ref "IC8") (pin "15") (pinfunction "G_15") (pintype "input"))
      (node (ref "IC9") (pin "15") (pinfunction "G_15") (pintype "input"))
      (node (ref "IC9") (pin "3") (pinfunction "1B_3") (pintype "input"))
      (node (ref "IC9") (pin "6") (pinfunction "2B_6") (pintype "input"))
      (node (ref "SJ1") (pin "3") (pinfunction "3_3") (pintype "passive"))
    )
    (net (code "90") (name "LIC") (class "Default")
      (node (ref "HDR1") (pin "38") (pinfunction "LIC_38") (pintype "output"))
      (node (ref "IC6") (pin "38") (pinfunction "LIC_38") (pintype "output"))
    )
    (net (code "91") (name "MMU_EN") (class "Default")
      (node (ref "IC17") (pin "13") (pinfunction "I2_13") (pintype "input"))
      (node (ref "IC2") (pin "5") (pinfunction "Q_5") (pintype "output"))
    )
    (net (code "92") (name "N$32") (class "Default")
      (node (ref "IC19") (pin "15") (pinfunction "Y4_15") (pintype "tri_state"))
    )
    (net (code "93") (name "N$33") (class "Default")
      (node (ref "IC19") (pin "14") (pinfunction "Y5_14") (pintype "tri_state"))
    )
    (net (code "94") (name "N$34") (class "Default")
      (node (ref "IC19") (pin "13") (pinfunction "Y6_13") (pintype "tri_state"))
    )
    (net (code "95") (name "N$35") (class "Default")
      (node (ref "IC19") (pin "12") (pinfunction "Y7_12") (pintype "tri_state"))
    )
    (net (code "96") (name "N$36") (class "Default")
      (node (ref "IC19") (pin "11") (pinfunction "Y8_11") (pintype "tri_state"))
    )
    (net (code "97") (name "N$40") (class "Default")
      (node (ref "IC19") (pin "5") (pinfunction "A4_5") (pintype "input"))
    )
    (net (code "98") (name "N$41") (class "Default")
      (node (ref "IC19") (pin "6") (pinfunction "A5_6") (pintype "input"))
    )
    (net (code "99") (name "N$42") (class "Default")
      (node (ref "IC19") (pin "7") (pinfunction "A6_7") (pintype "input"))
    )
    (net (code "100") (name "N$43") (class "Default")
      (node (ref "IC19") (pin "8") (pinfunction "A7_8") (pintype "input"))
    )
    (net (code "101") (name "N$44") (class "Default")
      (node (ref "IC19") (pin "9") (pinfunction "A8_9") (pintype "input"))
    )
    (net (code "102") (name "Net-(IC8A-1B)") (class "Default")
      (node (ref "IC8") (pin "3") (pinfunction "1B_3") (pintype "input"))
      (node (ref "IC9") (pin "4") (pinfunction "1Y_4") (pintype "output"))
    )
    (net (code "103") (name "Net-(IC8A-2B)") (class "Default")
      (node (ref "IC8") (pin "6") (pinfunction "2B_6") (pintype "input"))
      (node (ref "IC9") (pin "7") (pinfunction "2Y_7") (pintype "output"))
    )
    (net (code "104") (name "Q") (class "Default")
      (node (ref "HDR1") (pin "35") (pinfunction "Q_35") (pintype "input"))
      (node (ref "IC6") (pin "35") (pinfunction "Q_35") (pintype "input"))
    )
    (net (code "105") (name "TASK") (class "Default")
      (node (ref "IC1") (pin "5") (pinfunction "Q_5") (pintype "output"))
      (node (ref "IC3") (pin "17") (pinfunction "A4_17") (pintype "input"))
    )
    (net (code "106") (name "TSC") (class "Default")
      (node (ref "HDR1") (pin "39") (pinfunction "TSC_39") (pintype "open_collector"))
      (node (ref "IC6") (pin "39") (pinfunction "TSC_39") (pintype "open_collector"))
    )
    (net (code "107") (name "VBANK0") (class "Default")
      (node (ref "IC10") (pin "9") (pinfunction "Q_9") (pintype "output"))
      (node (ref "IC8") (pin "2") (pinfunction "1A_2") (pintype "input"))
    )
    (net (code "108") (name "VBANK1") (class "Default")
      (node (ref "IC10") (pin "5") (pinfunction "Q_5") (pintype "output"))
      (node (ref "IC8") (pin "5") (pinfunction "2A_5") (pintype "input"))
    )
    (net (code "109") (name "VCC") (class "Default")
      (node (ref "C1") (pin "1") (pinfunction "1_1") (pintype "passive"))
      (node (ref "C10") (pin "1") (pinfunction "1_1") (pintype "passive"))
      (node (ref "C11") (pin "1") (pinfunction "1_1") (pintype "passive"))
      (node (ref "C12") (pin "1") (pinfunction "1_1") (pintype "passive"))
      (node (ref "C13") (pin "1") (pinfunction "1_1") (pintype "passive"))
      (node (ref "C14") (pin "1") (pinfunction "1_1") (pintype "passive"))
      (node (ref "C15") (pin "1") (pinfunction "1_1") (pintype "passive"))
      (node (ref "C16") (pin "1") (pinfunction "1_1") (pintype "passive"))
      (node (ref "C17") (pin "1") (pinfunction "1_1") (pintype "passive"))
      (node (ref "C18") (pin "1") (pinfunction "1_1") (pintype "passive"))
      (node (ref "C19") (pin "1") (pinfunction "1_1") (pintype "passive"))
      (node (ref "C2") (pin "1") (pinfunction "1_1") (pintype "passive"))
      (node (ref "C3") (pin "1") (pinfunction "1_1") (pintype "passive"))
      (node (ref "C4") (pin "1") (pinfunction "1_1") (pintype "passive"))
      (node (ref "C5") (pin "1") (pinfunction "1_1") (pintype "passive"))
      (node (ref "C7") (pin "1") (pinfunction "1_1") (pintype "passive"))
      (node (ref "C8") (pin "1") (pinfunction "1_1") (pintype "passive"))
      (node (ref "C9") (pin "1") (pinfunction "1_1") (pintype "passive"))
      (node (ref "IC1") (pin "10") (pinfunction "PRE_10") (pintype "input"))
      (node (ref "IC1") (pin "4") (pinfunction "PRE_4") (pintype "input"))
      (node (ref "IC10") (pin "10") (pinfunction "PRE_10") (pintype "input"))
      (node (ref "IC10") (pin "4") (pinfunction "PRE_4") (pintype "input"))
      (node (ref "IC17") (pin "11") (pinfunction "I2_11") (pintype "input"))
      (node (ref "IC17") (pin "3") (pinfunction "I0_3") (pintype "input"))
      (node (ref "IC17") (pin "5") (pinfunction "I2_5") (pintype "input"))
      (node (ref "IC17") (pin "9") (pinfunction "I0_9") (pintype "input"))
      (node (ref "IC2") (pin "4") (pinfunction "PRE_4") (pintype "input"))
      (node (ref "R1") (pin "2") (pinfunction "2_2") (pintype "passive"))
    )
    (net (code "110") (name "unconnected-(IC1A-~{Q}-Pad6)") (class "Default")
      (node (ref "IC1") (pin "6") (pinfunction "~{Q}_6") (pintype "output"))
    )
    (net (code "111") (name "unconnected-(IC2B-CLK-Pad11)") (class "Default")
      (node (ref "IC2") (pin "11") (pinfunction "CLK_11") (pintype "input"))
    )
    (net (code "112") (name "unconnected-(IC2B-D-Pad12)") (class "Default")
      (node (ref "IC2") (pin "12") (pinfunction "D_12") (pintype "input"))
    )
    (net (code "113") (name "unconnected-(IC2B-PRE-Pad10)") (class "Default")
      (node (ref "IC2") (pin "10") (pinfunction "PRE_10") (pintype "input"))
    )
    (net (code "114") (name "unconnected-(IC2B-Q-Pad9)") (class "Default")
      (node (ref "IC2") (pin "9") (pinfunction "Q_9") (pintype "output"))
    )
    (net (code "115") (name "unconnected-(IC2B-~{Q}-Pad8)") (class "Default")
      (node (ref "IC2") (pin "8") (pinfunction "~{Q}_8") (pintype "output"))
    )
    (net (code "116") (name "unconnected-(IC5A-D2-Pad13)") (class "Default")
      (node (ref "IC5") (pin "13") (pinfunction "D2_13") (pintype "bidirectional"))
    )
    (net (code "117") (name "unconnected-(IC5A-D3-Pad15)") (class "Default")
      (node (ref "IC5") (pin "15") (pinfunction "D3_15") (pintype "bidirectional"))
    )
    (net (code "118") (name "unconnected-(IC5A-D4-Pad16)") (class "Default")
      (node (ref "IC5") (pin "16") (pinfunction "D4_16") (pintype "bidirectional"))
    )
    (net (code "119") (name "unconnected-(IC5A-D5-Pad17)") (class "Default")
      (node (ref "IC5") (pin "17") (pinfunction "D5_17") (pintype "bidirectional"))
    )
    (net (code "120") (name "unconnected-(IC5A-D6-Pad18)") (class "Default")
      (node (ref "IC5") (pin "18") (pinfunction "D6_18") (pintype "bidirectional"))
    )
    (net (code "121") (name "unconnected-(IC5A-D7-Pad19)") (class "Default")
      (node (ref "IC5") (pin "19") (pinfunction "D7_19") (pintype "bidirectional"))
    )
    (net (code "122") (name "unconnected-(IC7A-A3-Pad6)") (class "Default")
      (node (ref "IC7") (pin "6") (pinfunction "A3_6") (pintype "input"))
    )
    (net (code "123") (name "unconnected-(IC7A-A4-Pad8)") (class "Default")
      (node (ref "IC7") (pin "8") (pinfunction "A4_8") (pintype "input"))
    )
    (net (code "124") (name "unconnected-(IC7A-Y3-Pad14)") (class "Default")
      (node (ref "IC7") (pin "14") (pinfunction "Y3_14") (pintype "tri_state"))
    )
    (net (code "125") (name "unconnected-(IC7A-Y4-Pad12)") (class "Default")
      (node (ref "IC7") (pin "12") (pinfunction "Y4_12") (pintype "tri_state"))
    )
    (net (code "126") (name "unconnected-(IC7B-Y1-Pad9)") (class "Default")
      (node (ref "IC7") (pin "9") (pinfunction "Y1_9") (pintype "tri_state"))
    )
    (net (code "127") (name "unconnected-(IC7B-Y2-Pad7)") (class "Default")
      (node (ref "IC7") (pin "7") (pinfunction "Y2_7") (pintype "tri_state"))
    )
    (net (code "128") (name "unconnected-(IC7B-Y3-Pad5)") (class "Default")
      (node (ref "IC7") (pin "5") (pinfunction "Y3_5") (pintype "tri_state"))
    )
    (net (code "129") (name "unconnected-(IC7B-Y4-Pad3)") (class "Default")
      (node (ref "IC7") (pin "3") (pinfunction "Y4_3") (pintype "tri_state"))
    )
    (net (code "130") (name "unconnected-(IC8A-3A-Pad11)") (class "Default")
      (node (ref "IC8") (pin "11") (pinfunction "3A_11") (pintype "input"))
    )
    (net (code "131") (name "unconnected-(IC8A-3B-Pad10)") (class "Default")
      (node (ref "IC8") (pin "10") (pinfunction "3B_10") (pintype "input"))
    )
    (net (code "132") (name "unconnected-(IC8A-3Y-Pad9)") (class "Default")
      (node (ref "IC8") (pin "9") (pinfunction "3Y_9") (pintype "output"))
    )
    (net (code "133") (name "unconnected-(IC8A-4A-Pad14)") (class "Default")
      (node (ref "IC8") (pin "14") (pinfunction "4A_14") (pintype "input"))
    )
    (net (code "134") (name "unconnected-(IC8A-4B-Pad13)") (class "Default")
      (node (ref "IC8") (pin "13") (pinfunction "4B_13") (pintype "input"))
    )
    (net (code "135") (name "unconnected-(IC8A-4Y-Pad12)") (class "Default")
      (node (ref "IC8") (pin "12") (pinfunction "4Y_12") (pintype "output"))
    )
    (net (code "136") (name "unconnected-(IC9A-3A-Pad11)") (class "Default")
      (node (ref "IC9") (pin "11") (pinfunction "3A_11") (pintype "input"))
    )
    (net (code "137") (name "unconnected-(IC9A-3B-Pad10)") (class "Default")
      (node (ref "IC9") (pin "10") (pinfunction "3B_10") (pintype "input"))
    )
    (net (code "138") (name "unconnected-(IC9A-3Y-Pad9)") (class "Default")
      (node (ref "IC9") (pin "9") (pinfunction "3Y_9") (pintype "output"))
    )
    (net (code "139") (name "unconnected-(IC9A-4A-Pad14)") (class "Default")
      (node (ref "IC9") (pin "14") (pinfunction "4A_14") (pintype "input"))
    )
    (net (code "140") (name "unconnected-(IC9A-4B-Pad13)") (class "Default")
      (node (ref "IC9") (pin "13") (pinfunction "4B_13") (pintype "input"))
    )
    (net (code "141") (name "unconnected-(IC9A-4Y-Pad12)") (class "Default")
      (node (ref "IC9") (pin "12") (pinfunction "4Y_12") (pintype "output"))
    )
    (net (code "142") (name "unconnected-(IC10A-~{Q}-Pad6)") (class "Default")
      (node (ref "IC10") (pin "6") (pinfunction "~{Q}_6") (pintype "output"))
    )
    (net (code "143") (name "unconnected-(IC10B-~{Q}-Pad8)") (class "Default")
      (node (ref "IC10") (pin "8") (pinfunction "~{Q}_8") (pintype "output"))
    )
    (net (code "144") (name "unconnected-(IC12A-Y2-Pad13)") (class "Default")
      (node (ref "IC12") (pin "13") (pinfunction "Y2_13") (pintype "output"))
    )
    (net (code "145") (name "unconnected-(IC12A-Y3-Pad12)") (class "Default")
      (node (ref "IC12") (pin "12") (pinfunction "Y3_12") (pintype "output"))
    )
    (net (code "146") (name "unconnected-(IC12A-Y4-Pad11)") (class "Default")
      (node (ref "IC12") (pin "11") (pinfunction "Y4_11") (pintype "output"))
    )
    (net (code "147") (name "unconnected-(IC12A-Y5-Pad10)") (class "Default")
      (node (ref "IC12") (pin "10") (pinfunction "Y5_10") (pintype "output"))
    )
    (net (code "148") (name "unconnected-(IC12A-Y6-Pad9)") (class "Default")
      (node (ref "IC12") (pin "9") (pinfunction "Y6_9") (pintype "output"))
    )
    (net (code "149") (name "unconnected-(IC12A-Y7-Pad7)") (class "Default")
      (node (ref "IC12") (pin "7") (pinfunction "Y7_7") (pintype "output"))
    )
    (net (code "150") (name "unconnected-(IC13A-Y0-Pad15)") (class "Default")
      (node (ref "IC13") (pin "15") (pinfunction "Y0_15") (pintype "output"))
    )
    (net (code "151") (name "unconnected-(IC13A-Y3-Pad12)") (class "Default")
      (node (ref "IC13") (pin "12") (pinfunction "Y3_12") (pintype "output"))
    )
    (net (code "152") (name "unconnected-(IC13A-Y4-Pad11)") (class "Default")
      (node (ref "IC13") (pin "11") (pinfunction "Y4_11") (pintype "output"))
    )
    (net (code "153") (name "unconnected-(IC13A-Y5-Pad10)") (class "Default")
      (node (ref "IC13") (pin "10") (pinfunction "Y5_10") (pintype "output"))
    )
    (net (code "154") (name "unconnected-(IC13A-Y6-Pad9)") (class "Default")
      (node (ref "IC13") (pin "9") (pinfunction "Y6_9") (pintype "output"))
    )
    (net (code "155") (name "unconnected-(IC13A-Y7-Pad7)") (class "Default")
      (node (ref "IC13") (pin "7") (pinfunction "Y7_7") (pintype "output"))
    )
    (net (code "156") (name "unconnected-(IC14A-Y0-Pad15)") (class "Default")
      (node (ref "IC14") (pin "15") (pinfunction "Y0_15") (pintype "output"))
    )
    (net (code "157") (name "unconnected-(IC14A-Y1-Pad14)") (class "Default")
      (node (ref "IC14") (pin "14") (pinfunction "Y1_14") (pintype "output"))
    )
    (net (code "158") (name "unconnected-(IC14A-Y2-Pad13)") (class "Default")
      (node (ref "IC14") (pin "13") (pinfunction "Y2_13") (pintype "output"))
    )
    (net (code "159") (name "unconnected-(IC14A-Y4-Pad11)") (class "Default")
      (node (ref "IC14") (pin "11") (pinfunction "Y4_11") (pintype "output"))
    )
    (net (code "160") (name "unconnected-(IC14A-Y5-Pad10)") (class "Default")
      (node (ref "IC14") (pin "10") (pinfunction "Y5_10") (pintype "output"))
    )
    (net (code "161") (name "unconnected-(IC14A-Y6-Pad9)") (class "Default")
      (node (ref "IC14") (pin "9") (pinfunction "Y6_9") (pintype "output"))
    )
    (net (code "162") (name "unconnected-(IC14A-Y7-Pad7)") (class "Default")
      (node (ref "IC14") (pin "7") (pinfunction "Y7_7") (pintype "output"))
    )
  )
)
